# psram.net
KiCad netlist of a schematic drawn in Altium Designer
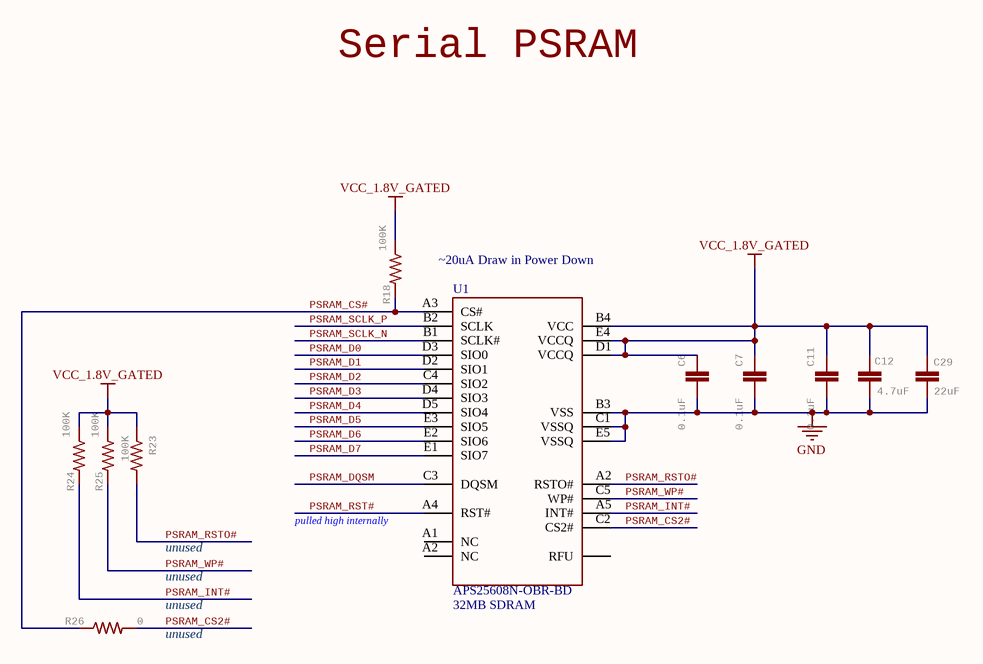
[diagram p0: psram.SchDoc]

(export (version "E")
  (design (tool "Eeschema 10.0.6"))
  (components
    (comp (ref "C6")
      (value "0.1uF")
      (footprint "0402-CAP")
      (description "CAPACITOR, European symbol")
      (fields (field (name "MPN") "C0402C104Z4VAC"))
      (libsource (lib "openmv-ae3") (part "C-EUC0201"))
    )
    (comp (ref "C7")
      (value "0.1uF")
      (footprint "0402-CAP")
      (description "CAPACITOR, European symbol")
      (fields (field (name "MPN") "C0402C104Z4VAC"))
      (libsource (lib "openmv-ae3") (part "C-EUC0201"))
    )
    (comp (ref "C11")
      (value "0.1uF")
      (footprint "0402-CAP")
      (description "CAPACITOR, European symbol")
      (fields (field (name "MPN") "C0402C104Z4VAC"))
      (libsource (lib "openmv-ae3") (part "C-EUC0201"))
    )
    (comp (ref "C12")
      (value "4.7uF")
      (footprint "0402-CAP")
      (description "CapacitorStandard 0603 ceramic capacitor, and 0.1\" leaded capacitor.")
      (fields (field (name "MPN") "JMK105BBJ475MV-F") (field (name "LIBRARYNAME") "sfe"))
      (libsource (lib "openmv-ae3") (part "CAP0402-CAP"))
    )
    (comp (ref "C29")
      (value "22uF")
      (footprint "0805")
      (fields (field (name "MPN") "CL21A226MQQNNNE"))
      (libsource (lib "openmv-ae3") (part "22UF-0805-6.3V-20%"))
    )
    (comp (ref "R18")
      (value "100K")
      (footprint "0402-RES")
      (description "ResistorBasic schematic elements and footprints for 0603, 1206, and PTH resistors.")
      (fields (field (name "MPN") "AC0402FR-07100KL") (field (name "LIBRARYNAME") "sfe"))
      (libsource (lib "openmv-ae3") (part "RESISTOR0402-RES"))
    )
    (comp (ref "R23")
      (value "100K")
      (footprint "0402-RES")
      (description "ResistorBasic schematic elements and footprints for 0603, 1206, and PTH resistors.")
      (fields (field (name "MPN") "AC0402FR-07100KL") (field (name "LIBRARYNAME") "sfe"))
      (libsource (lib "openmv-ae3") (part "RESISTOR0402-RES"))
    )
    (comp (ref "R24")
      (value "100K")
      (footprint "0402-RES")
      (description "ResistorBasic schematic elements and footprints for 0603, 1206, and PTH resistors.")
      (fields (field (name "MPN") "AC0402FR-07100KL") (field (name "LIBRARYNAME") "sfe"))
      (libsource (lib "openmv-ae3") (part "RESISTOR0402-RES"))
    )
    (comp (ref "R25")
      (value "100K")
      (footprint "0402-RES")
      (description "ResistorBasic schematic elements and footprints for 0603, 1206, and PTH resistors.")
      (fields (field (name "MPN") "AC0402FR-07100KL") (field (name "LIBRARYNAME") "sfe"))
      (libsource (lib "openmv-ae3") (part "RESISTOR0402-RES"))
    )
    (comp (ref "R26")
      (value "0")
      (footprint "0402-RES")
      (description "ResistorBasic schematic elements and footprints for 0603, 1206, and PTH resistors.")
      (fields (field (name "MPN") "RC0402JR-070R") (field (name "LIBRARYNAME") "sfe"))
      (libsource (lib "openmv-ae3") (part "RESISTOR0402-RES"))
    )
    (comp (ref "U1")
      (value "APS25608N-OBR-BD")
      (footprint "24-TBGA")
      (fields (field (name "MF") "ISSI"))
      (libsource (lib "openmv-ae3") (part "IS66WVO32M8DALL-200BLI-TR"))
    )
  )
  (nets
    (net (code "1") (name "/PSRAM_CS#") (class "Default")
      (node (ref "R18") (pin "2") (pinfunction "2_2") (pintype "passive"))
      (node (ref "R26") (pin "1") (pinfunction "1_1") (pintype "passive"))
      (node (ref "U1") (pin "A3") (pinfunction "CS#_A3") (pintype "passive"))
    )
    (net (code "2") (name "/PSRAM_CS2#") (class "Default")
      (node (ref "R26") (pin "2") (pinfunction "2_2") (pintype "passive"))
      (node (ref "U1") (pin "C2") (pinfunction "CS2#_C2") (pintype "passive"))
    )
    (net (code "3") (name "/PSRAM_D0") (class "Default")
      (node (ref "U1") (pin "D3") (pinfunction "SIO0_D3") (pintype "passive"))
    )
    (net (code "4") (name "/PSRAM_D1") (class "Default")
      (node (ref "U1") (pin "D2") (pinfunction "SIO1_D2") (pintype "passive"))
    )
    (net (code "5") (name "/PSRAM_D2") (class "Default")
      (node (ref "U1") (pin "C4") (pinfunction "SIO2_C4") (pintype "passive"))
    )
    (net (code "6") (name "/PSRAM_D3") (class "Default")
      (node (ref "U1") (pin "D4") (pinfunction "SIO3_D4") (pintype "passive"))
    )
    (net (code "7") (name "/PSRAM_D4") (class "Default")
      (node (ref "U1") (pin "D5") (pinfunction "SIO4_D5") (pintype "passive"))
    )
    (net (code "8") (name "/PSRAM_D5") (class "Default")
      (node (ref "U1") (pin "E3") (pinfunction "SIO5_E3") (pintype "passive"))
    )
    (net (code "9") (name "/PSRAM_D6") (class "Default")
      (node (ref "U1") (pin "E2") (pinfunction "SIO6_E2") (pintype "passive"))
    )
    (net (code "10") (name "/PSRAM_D7") (class "Default")
      (node (ref "U1") (pin "E1") (pinfunction "SIO7_E1") (pintype "passive"))
    )
    (net (code "11") (name "/PSRAM_DQSM") (class "Default")
      (node (ref "U1") (pin "C3") (pinfunction "DQSM_C3") (pintype "passive"))
    )
    (net (code "12") (name "/PSRAM_INT#") (class "Default")
      (node (ref "R24") (pin "2") (pinfunction "2_2") (pintype "passive"))
      (node (ref "U1") (pin "A5") (pinfunction "INT#_A5") (pintype "passive"))
    )
    (net (code "13") (name "/PSRAM_RST#") (class "Default")
      (node (ref "U1") (pin "A4") (pinfunction "RST#_A4") (pintype "passive"))
    )
    (net (code "14") (name "/PSRAM_RSTO#") (class "Default")
      (node (ref "R23") (pin "2") (pinfunction "2_2") (pintype "passive"))
      (node (ref "U1") (pin "A2") (pinfunction "RSTO#_A2") (pintype "passive"))
    )
    (net (code "15") (name "/PSRAM_SCLK_N") (class "Default")
      (node (ref "U1") (pin "B1") (pinfunction "SCLK#_B1") (pintype "passive"))
    )
    (net (code "16") (name "/PSRAM_SCLK_P") (class "Default")
      (node (ref "U1") (pin "B2") (pinfunction "SCLK_B2") (pintype "passive"))
    )
    (net (code "17") (name "/PSRAM_WP#") (class "Default")
      (node (ref "R25") (pin "2") (pinfunction "2_2") (pintype "passive"))
      (node (ref "U1") (pin "C5") (pinfunction "WP#_C5") (pintype "passive"))
    )
    (net (code "18") (name "GND") (class "Default")
      (node (ref "C11") (pin "2") (pinfunction "2_2") (pintype "passive"))
      (node (ref "C12") (pin "1") (pinfunction "1_1") (pintype "passive"))
      (node (ref "C29") (pin "1") (pinfunction "1_1") (pintype "passive"))
      (node (ref "C6") (pin "2") (pinfunction "2_2") (pintype "passive"))
      (node (ref "C7") (pin "2") (pinfunction "2_2") (pintype "passive"))
      (node (ref "U1") (pin "B3") (pinfunction "VSS_B3") (pintype "passive"))
      (node (ref "U1") (pin "C1") (pinfunction "VSSQ_C1") (pintype "passive"))
      (node (ref "U1") (pin "E5") (pinfunction "VSSQ_E5") (pintype "passive"))
    )
    (net (code "19") (name "VCC_1.8V_GATED") (class "Default")
      (node (ref "C11") (pin "1") (pinfunction "1_1") (pintype "passive"))
      (node (ref "C12") (pin "2") (pinfunction "2_2") (pintype "passive"))
      (node (ref "C29") (pin "2") (pinfunction "2_2") (pintype "passive"))
      (node (ref "C6") (pin "1") (pinfunction "1_1") (pintype "passive"))
      (node (ref "C7") (pin "1") (pinfunction "1_1") (pintype "passive"))
      (node (ref "R18") (pin "1") (pinfunction "1_1") (pintype "passive"))
      (node (ref "R23") (pin "1") (pinfunction "1_1") (pintype "passive"))
      (node (ref "R24") (pin "1") (pinfunction "1_1") (pintype "passive"))
      (node (ref "R25") (pin "1") (pinfunction "1_1") (pintype "passive"))
      (node (ref "U1") (pin "B4") (pinfunction "VCC_B4") (pintype "passive"))
      (node (ref "U1") (pin "D1") (pinfunction "VCCQ_D1") (pintype "passive"))
      (node (ref "U1") (pin "E4") (pinfunction "VCCQ_E4") (pintype "passive"))
    )
    (net (code "20") (name "unconnected-(U1-NC-PadA1)") (class "Default")
      (node (ref "U1") (pin "A1") (pinfunction "NC_A1") (pintype "passive"))
    )
    (net (code "21") (name "unconnected-(U1-NC-PadA2)") (class "Default")
      (node (ref "U1") (pin "A2") (pinfunction "NC_A2") (pintype "passive"))
    )
    (net (code "22") (name "unconnected-(U1-RFU-PadC5)") (class "Default")
      (node (ref "U1") (pin "C5") (pinfunction "RFU_C5") (pintype "passive"))
    )
  )
)
